# KNOT_v1_0_disp.net
KiCad netlist of a schematic drawn in EAGLE
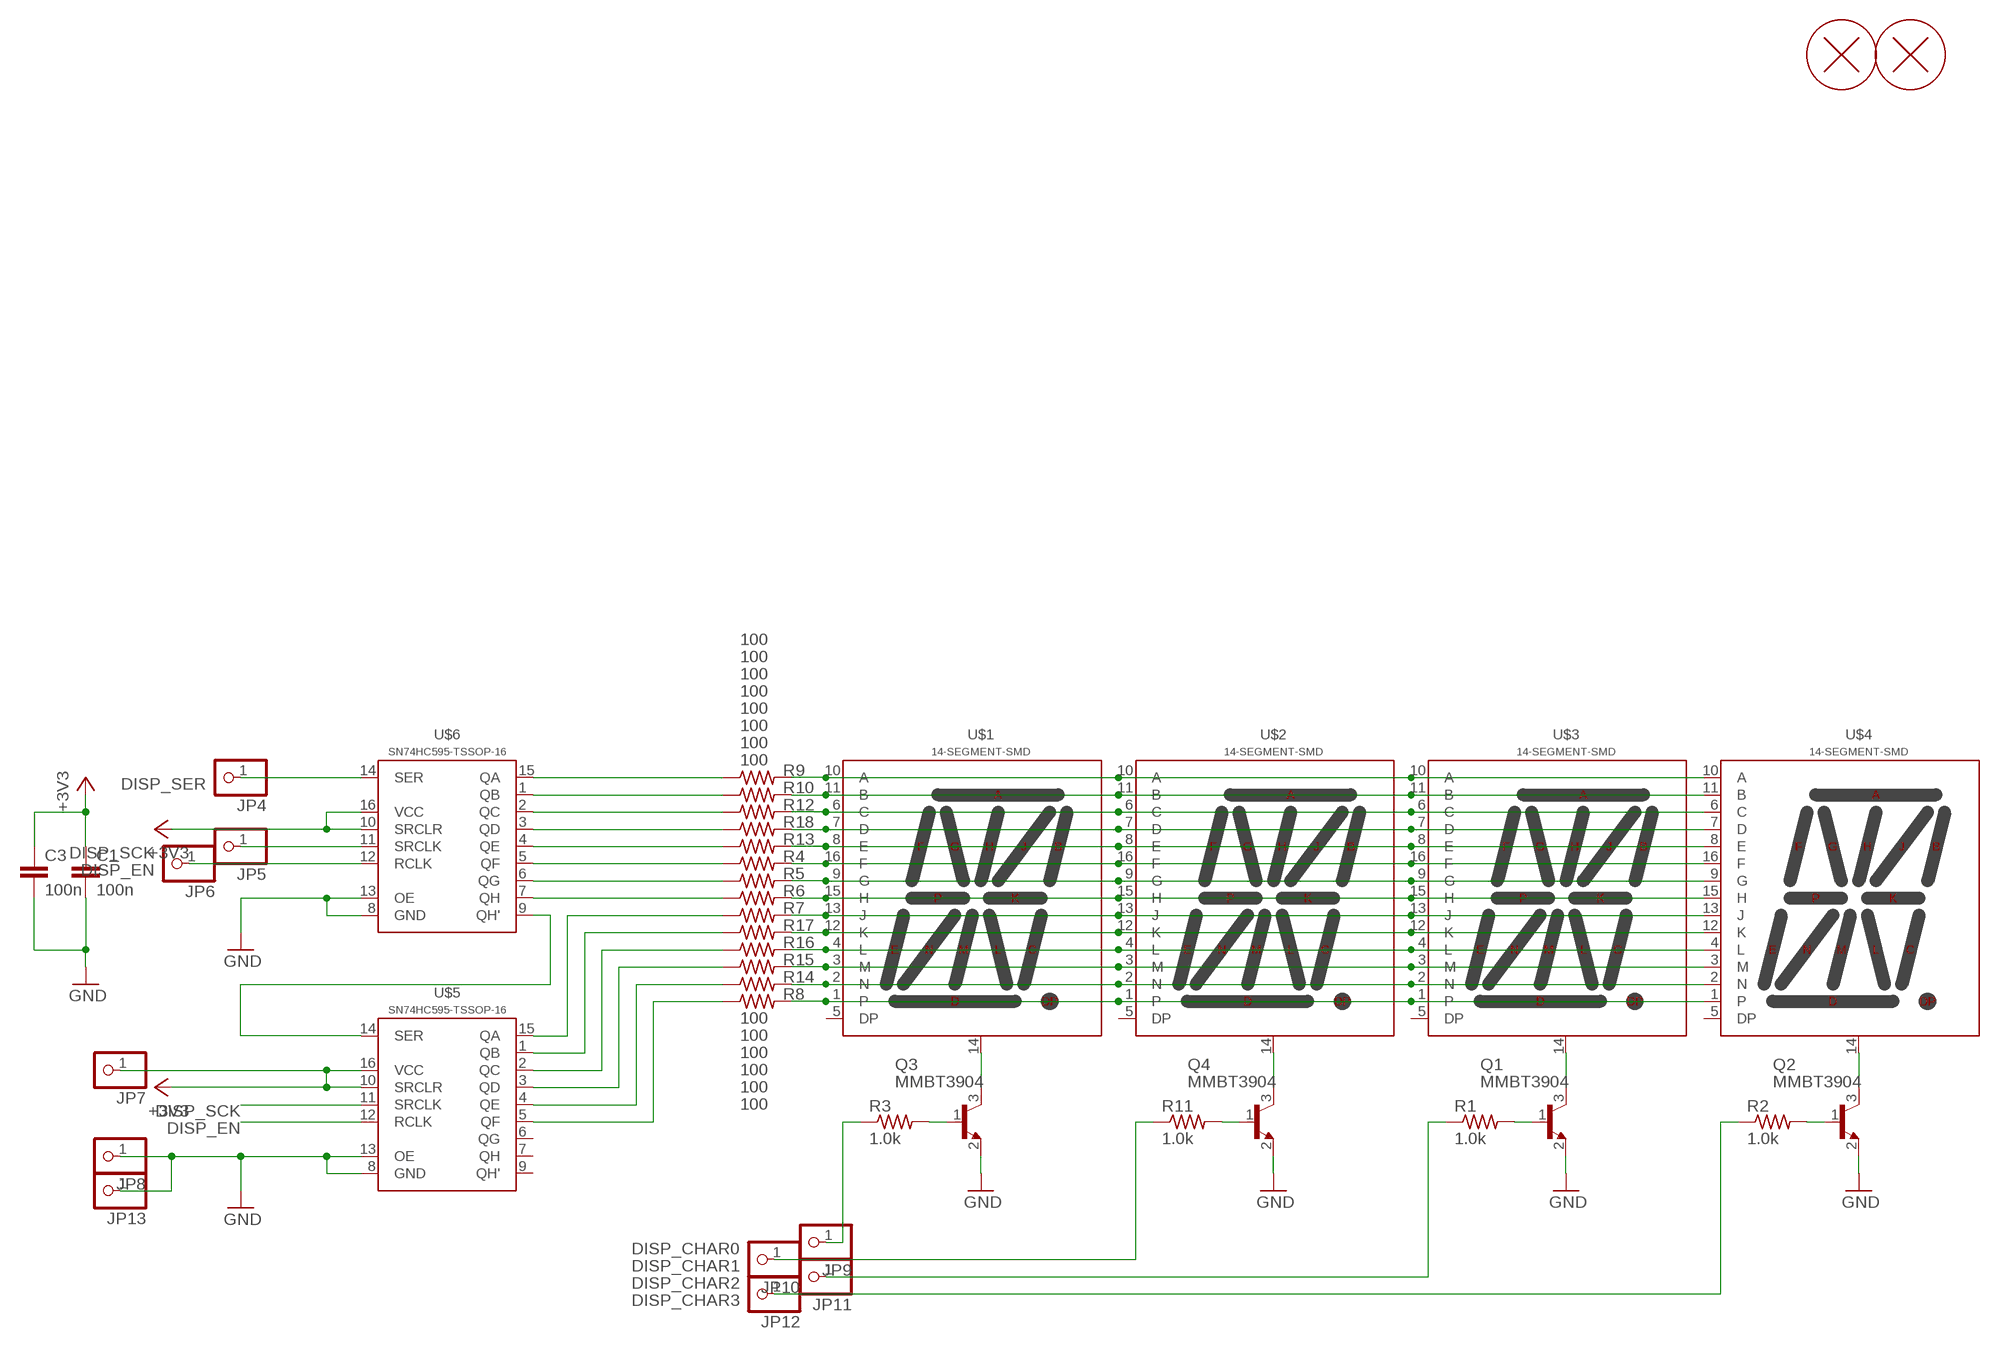
[diagram p0: schematic, sheet 1]

(export (version "E")
  (design (tool "Eeschema 10.0.6"))
  (components
    (comp (ref "C1")
      (value "100n")
      (footprint "eagle-import:RESISTOR_0603")
      (libsource (lib "eagle-import") (part "CAPACITOR"))
    )
    (comp (ref "C3")
      (value "100n")
      (footprint "eagle-import:RESISTOR_0603")
      (libsource (lib "eagle-import") (part "CAPACITOR"))
    )
    (comp (ref "H1")
      (value "PCB_SCREW")
      (footprint "eagle-import:PCB_SCREW")
      (libsource (lib "eagle-import") (part "PCB_SCREW"))
    )
    (comp (ref "H2")
      (value "PCB_SCREW")
      (footprint "eagle-import:PCB_SCREW")
      (libsource (lib "eagle-import") (part "PCB_SCREW"))
    )
    (comp (ref "JP4")
      (value "PINHD-1X1")
      (footprint "eagle-import:1X01")
      (libsource (lib "eagle-import") (part "PINHD-1X1"))
    )
    (comp (ref "JP5")
      (value "PINHD-1X1")
      (footprint "eagle-import:1X01")
      (libsource (lib "eagle-import") (part "PINHD-1X1"))
    )
    (comp (ref "JP6")
      (value "PINHD-1X1")
      (footprint "eagle-import:1X01")
      (libsource (lib "eagle-import") (part "PINHD-1X1"))
    )
    (comp (ref "JP7")
      (value "PINHD-1X1")
      (footprint "eagle-import:1X01")
      (libsource (lib "eagle-import") (part "PINHD-1X1"))
    )
    (comp (ref "JP8")
      (value "PINHD-1X1")
      (footprint "eagle-import:1X01")
      (libsource (lib "eagle-import") (part "PINHD-1X1"))
    )
    (comp (ref "JP9")
      (value "PINHD-1X1")
      (footprint "eagle-import:1X01")
      (libsource (lib "eagle-import") (part "PINHD-1X1"))
    )
    (comp (ref "JP10")
      (value "PINHD-1X1")
      (footprint "eagle-import:1X01")
      (libsource (lib "eagle-import") (part "PINHD-1X1"))
    )
    (comp (ref "JP11")
      (value "PINHD-1X1")
      (footprint "eagle-import:1X01")
      (libsource (lib "eagle-import") (part "PINHD-1X1"))
    )
    (comp (ref "JP12")
      (value "PINHD-1X1")
      (footprint "eagle-import:1X01")
      (libsource (lib "eagle-import") (part "PINHD-1X1"))
    )
    (comp (ref "JP13")
      (value "PINHD-1X1")
      (footprint "eagle-import:1X01")
      (libsource (lib "eagle-import") (part "PINHD-1X1"))
    )
    (comp (ref "Q1")
      (value "MMBT3904")
      (footprint "eagle-import:SOT23")
      (libsource (lib "eagle-import") (part "MMBT3904SOT23"))
    )
    (comp (ref "Q2")
      (value "MMBT3904")
      (footprint "eagle-import:SOT23")
      (libsource (lib "eagle-import") (part "MMBT3904SOT23"))
    )
    (comp (ref "Q3")
      (value "MMBT3904")
      (footprint "eagle-import:SOT23")
      (libsource (lib "eagle-import") (part "MMBT3904SOT23"))
    )
    (comp (ref "Q4")
      (value "MMBT3904")
      (footprint "eagle-import:SOT23")
      (libsource (lib "eagle-import") (part "MMBT3904SOT23"))
    )
    (comp (ref "R1")
      (value "1.0k")
      (footprint "eagle-import:RESISTOR_0603")
      (libsource (lib "eagle-import") (part "RESISTOR"))
    )
    (comp (ref "R2")
      (value "1.0k")
      (footprint "eagle-import:RESISTOR_0603")
      (libsource (lib "eagle-import") (part "RESISTOR"))
    )
    (comp (ref "R3")
      (value "1.0k")
      (footprint "eagle-import:RESISTOR_0603")
      (libsource (lib "eagle-import") (part "RESISTOR"))
    )
    (comp (ref "R4")
      (value "100")
      (footprint "eagle-import:RESISTOR_0603")
      (libsource (lib "eagle-import") (part "RESISTOR"))
    )
    (comp (ref "R5")
      (value "100")
      (footprint "eagle-import:RESISTOR_0603")
      (libsource (lib "eagle-import") (part "RESISTOR"))
    )
    (comp (ref "R6")
      (value "100")
      (footprint "eagle-import:RESISTOR_0603")
      (libsource (lib "eagle-import") (part "RESISTOR"))
    )
    (comp (ref "R7")
      (value "100")
      (footprint "eagle-import:RESISTOR_0603")
      (libsource (lib "eagle-import") (part "RESISTOR"))
    )
    (comp (ref "R8")
      (value "100")
      (footprint "eagle-import:RESISTOR_0603")
      (libsource (lib "eagle-import") (part "RESISTOR"))
    )
    (comp (ref "R9")
      (value "100")
      (footprint "eagle-import:RESISTOR_0603")
      (libsource (lib "eagle-import") (part "RESISTOR"))
    )
    (comp (ref "R10")
      (value "100")
      (footprint "eagle-import:RESISTOR_0603")
      (libsource (lib "eagle-import") (part "RESISTOR"))
    )
    (comp (ref "R11")
      (value "1.0k")
      (footprint "eagle-import:RESISTOR_0603")
      (libsource (lib "eagle-import") (part "RESISTOR"))
    )
    (comp (ref "R12")
      (value "100")
      (footprint "eagle-import:RESISTOR_0603")
      (libsource (lib "eagle-import") (part "RESISTOR"))
    )
    (comp (ref "R13")
      (value "100")
      (footprint "eagle-import:RESISTOR_0603")
      (libsource (lib "eagle-import") (part "RESISTOR"))
    )
    (comp (ref "R14")
      (value "100")
      (footprint "eagle-import:RESISTOR_0603")
      (libsource (lib "eagle-import") (part "RESISTOR"))
    )
    (comp (ref "R15")
      (value "100")
      (footprint "eagle-import:RESISTOR_0603")
      (libsource (lib "eagle-import") (part "RESISTOR"))
    )
    (comp (ref "R16")
      (value "100")
      (footprint "eagle-import:RESISTOR_0603")
      (libsource (lib "eagle-import") (part "RESISTOR"))
    )
    (comp (ref "R17")
      (value "100")
      (footprint "eagle-import:RESISTOR_0603")
      (libsource (lib "eagle-import") (part "RESISTOR"))
    )
    (comp (ref "R18")
      (value "100")
      (footprint "eagle-import:RESISTOR_0603")
      (libsource (lib "eagle-import") (part "RESISTOR"))
    )
    (comp (ref "U$1")
      (value "14-SEGMENT-SMD")
      (footprint "eagle-import:14-SEGMENT-0.4_-SMD")
      (libsource (lib "eagle-import") (part "14-SEGMENT-SMD"))
    )
    (comp (ref "U$2")
      (value "14-SEGMENT-SMD")
      (footprint "eagle-import:14-SEGMENT-0.4_-SMD")
      (libsource (lib "eagle-import") (part "14-SEGMENT-SMD"))
    )
    (comp (ref "U$3")
      (value "14-SEGMENT-SMD")
      (footprint "eagle-import:14-SEGMENT-0.4_-SMD")
      (libsource (lib "eagle-import") (part "14-SEGMENT-SMD"))
    )
    (comp (ref "U$4")
      (value "14-SEGMENT-SMD")
      (footprint "eagle-import:14-SEGMENT-0.4_-SMD")
      (libsource (lib "eagle-import") (part "14-SEGMENT-SMD"))
    )
    (comp (ref "U$5")
      (value "SN74HC595-TSSOP-16")
      (footprint "eagle-import:TSSOP-16")
      (libsource (lib "eagle-import") (part "SN74HC595-TSSOP-16"))
    )
    (comp (ref "U$6")
      (value "SN74HC595-TSSOP-16")
      (footprint "eagle-import:TSSOP-16")
      (libsource (lib "eagle-import") (part "SN74HC595-TSSOP-16"))
    )
  )
  (nets
    (net (code "1") (name "+3V3") (class "Default")
      (node (ref "C1") (pin "1") (pinfunction "1_1") (pintype "passive"))
      (node (ref "C3") (pin "1") (pinfunction "1_1") (pintype "passive"))
      (node (ref "JP7") (pin "1") (pinfunction "1_1") (pintype "passive"))
      (node (ref "U$5") (pin "10") (pinfunction "SRCLR_10") (pintype "bidirectional"))
      (node (ref "U$5") (pin "16") (pinfunction "VCC_16") (pintype "bidirectional"))
      (node (ref "U$6") (pin "10") (pinfunction "SRCLR_10") (pintype "bidirectional"))
      (node (ref "U$6") (pin "16") (pinfunction "VCC_16") (pintype "bidirectional"))
    )
    (net (code "2") (name "/DISP_CHAR0") (class "Default")
      (node (ref "JP9") (pin "1") (pinfunction "1_1") (pintype "passive"))
      (node (ref "R3") (pin "1") (pinfunction "1_1") (pintype "passive"))
    )
    (net (code "3") (name "/DISP_CHAR1") (class "Default")
      (node (ref "JP10") (pin "1") (pinfunction "1_1") (pintype "passive"))
      (node (ref "R11") (pin "1") (pinfunction "1_1") (pintype "passive"))
    )
    (net (code "4") (name "/DISP_CHAR2") (class "Default")
      (node (ref "JP11") (pin "1") (pinfunction "1_1") (pintype "passive"))
      (node (ref "R1") (pin "1") (pinfunction "1_1") (pintype "passive"))
    )
    (net (code "5") (name "/DISP_CHAR3") (class "Default")
      (node (ref "JP12") (pin "1") (pinfunction "1_1") (pintype "passive"))
      (node (ref "R2") (pin "1") (pinfunction "1_1") (pintype "passive"))
    )
    (net (code "6") (name "/DISP_EN") (class "Default")
      (node (ref "JP6") (pin "1") (pinfunction "1_1") (pintype "passive"))
      (node (ref "U$5") (pin "12") (pinfunction "RCLK_12") (pintype "bidirectional"))
      (node (ref "U$6") (pin "12") (pinfunction "RCLK_12") (pintype "bidirectional"))
    )
    (net (code "7") (name "/DISP_SCK") (class "Default")
      (node (ref "JP5") (pin "1") (pinfunction "1_1") (pintype "passive"))
      (node (ref "U$5") (pin "11") (pinfunction "SRCLK_11") (pintype "bidirectional"))
      (node (ref "U$6") (pin "11") (pinfunction "SRCLK_11") (pintype "bidirectional"))
    )
    (net (code "8") (name "/DISP_SER") (class "Default")
      (node (ref "JP4") (pin "1") (pinfunction "1_1") (pintype "passive"))
      (node (ref "U$6") (pin "14") (pinfunction "SER_14") (pintype "bidirectional"))
    )
    (net (code "9") (name "GND") (class "Default")
      (node (ref "C1") (pin "2") (pinfunction "2_2") (pintype "passive"))
      (node (ref "C3") (pin "2") (pinfunction "2_2") (pintype "passive"))
      (node (ref "JP13") (pin "1") (pinfunction "1_1") (pintype "passive"))
      (node (ref "JP8") (pin "1") (pinfunction "1_1") (pintype "passive"))
      (node (ref "Q1") (pin "2") (pinfunction "E_2") (pintype "passive"))
      (node (ref "Q2") (pin "2") (pinfunction "E_2") (pintype "passive"))
      (node (ref "Q3") (pin "2") (pinfunction "E_2") (pintype "passive"))
      (node (ref "Q4") (pin "2") (pinfunction "E_2") (pintype "passive"))
      (node (ref "U$5") (pin "13") (pinfunction "OE_13") (pintype "bidirectional"))
      (node (ref "U$5") (pin "8") (pinfunction "GND_8") (pintype "bidirectional"))
      (node (ref "U$6") (pin "13") (pinfunction "OE_13") (pintype "bidirectional"))
      (node (ref "U$6") (pin "8") (pinfunction "GND_8") (pintype "bidirectional"))
    )
    (net (code "10") (name "Net-(Q1-B)") (class "Default")
      (node (ref "Q1") (pin "1") (pinfunction "B_1") (pintype "passive"))
      (node (ref "R1") (pin "2") (pinfunction "2_2") (pintype "passive"))
    )
    (net (code "11") (name "Net-(Q1-C)") (class "Default")
      (node (ref "Q1") (pin "3") (pinfunction "C_3") (pintype "passive"))
      (node (ref "U$3") (pin "14") (pinfunction "CATHODE_14") (pintype "bidirectional"))
    )
    (net (code "12") (name "Net-(Q2-B)") (class "Default")
      (node (ref "Q2") (pin "1") (pinfunction "B_1") (pintype "passive"))
      (node (ref "R2") (pin "2") (pinfunction "2_2") (pintype "passive"))
    )
    (net (code "13") (name "Net-(Q2-C)") (class "Default")
      (node (ref "Q2") (pin "3") (pinfunction "C_3") (pintype "passive"))
      (node (ref "U$4") (pin "14") (pinfunction "CATHODE_14") (pintype "bidirectional"))
    )
    (net (code "14") (name "Net-(Q3-B)") (class "Default")
      (node (ref "Q3") (pin "1") (pinfunction "B_1") (pintype "passive"))
      (node (ref "R3") (pin "2") (pinfunction "2_2") (pintype "passive"))
    )
    (net (code "15") (name "Net-(Q3-C)") (class "Default")
      (node (ref "Q3") (pin "3") (pinfunction "C_3") (pintype "passive"))
      (node (ref "U$1") (pin "14") (pinfunction "CATHODE_14") (pintype "bidirectional"))
    )
    (net (code "16") (name "Net-(Q4-B)") (class "Default")
      (node (ref "Q4") (pin "1") (pinfunction "B_1") (pintype "passive"))
      (node (ref "R11") (pin "2") (pinfunction "2_2") (pintype "passive"))
    )
    (net (code "17") (name "Net-(Q4-C)") (class "Default")
      (node (ref "Q4") (pin "3") (pinfunction "C_3") (pintype "passive"))
      (node (ref "U$2") (pin "14") (pinfunction "CATHODE_14") (pintype "bidirectional"))
    )
    (net (code "18") (name "Net-(U$1-A)") (class "Default")
      (node (ref "R9") (pin "2") (pinfunction "2_2") (pintype "passive"))
      (node (ref "U$1") (pin "10") (pinfunction "A_10") (pintype "bidirectional"))
      (node (ref "U$2") (pin "10") (pinfunction "A_10") (pintype "bidirectional"))
      (node (ref "U$3") (pin "10") (pinfunction "A_10") (pintype "bidirectional"))
      (node (ref "U$4") (pin "10") (pinfunction "A_10") (pintype "bidirectional"))
    )
    (net (code "19") (name "Net-(U$1-B)") (class "Default")
      (node (ref "R10") (pin "2") (pinfunction "2_2") (pintype "passive"))
      (node (ref "U$1") (pin "11") (pinfunction "B_11") (pintype "bidirectional"))
      (node (ref "U$2") (pin "11") (pinfunction "B_11") (pintype "bidirectional"))
      (node (ref "U$3") (pin "11") (pinfunction "B_11") (pintype "bidirectional"))
      (node (ref "U$4") (pin "11") (pinfunction "B_11") (pintype "bidirectional"))
    )
    (net (code "20") (name "Net-(U$1-C)") (class "Default")
      (node (ref "R12") (pin "2") (pinfunction "2_2") (pintype "passive"))
      (node (ref "U$1") (pin "6") (pinfunction "C_6") (pintype "bidirectional"))
      (node (ref "U$2") (pin "6") (pinfunction "C_6") (pintype "bidirectional"))
      (node (ref "U$3") (pin "6") (pinfunction "C_6") (pintype "bidirectional"))
      (node (ref "U$4") (pin "6") (pinfunction "C_6") (pintype "bidirectional"))
    )
    (net (code "21") (name "Net-(U$1-D)") (class "Default")
      (node (ref "R18") (pin "2") (pinfunction "2_2") (pintype "passive"))
      (node (ref "U$1") (pin "7") (pinfunction "D_7") (pintype "bidirectional"))
      (node (ref "U$2") (pin "7") (pinfunction "D_7") (pintype "bidirectional"))
      (node (ref "U$3") (pin "7") (pinfunction "D_7") (pintype "bidirectional"))
      (node (ref "U$4") (pin "7") (pinfunction "D_7") (pintype "bidirectional"))
    )
    (net (code "22") (name "Net-(U$1-E)") (class "Default")
      (node (ref "R13") (pin "2") (pinfunction "2_2") (pintype "passive"))
      (node (ref "U$1") (pin "8") (pinfunction "E_8") (pintype "bidirectional"))
      (node (ref "U$2") (pin "8") (pinfunction "E_8") (pintype "bidirectional"))
      (node (ref "U$3") (pin "8") (pinfunction "E_8") (pintype "bidirectional"))
      (node (ref "U$4") (pin "8") (pinfunction "E_8") (pintype "bidirectional"))
    )
    (net (code "23") (name "Net-(U$1-F)") (class "Default")
      (node (ref "R4") (pin "2") (pinfunction "2_2") (pintype "passive"))
      (node (ref "U$1") (pin "16") (pinfunction "F_16") (pintype "bidirectional"))
      (node (ref "U$2") (pin "16") (pinfunction "F_16") (pintype "bidirectional"))
      (node (ref "U$3") (pin "16") (pinfunction "F_16") (pintype "bidirectional"))
      (node (ref "U$4") (pin "16") (pinfunction "F_16") (pintype "bidirectional"))
    )
    (net (code "24") (name "Net-(U$1-G)") (class "Default")
      (node (ref "R5") (pin "2") (pinfunction "2_2") (pintype "passive"))
      (node (ref "U$1") (pin "9") (pinfunction "G_9") (pintype "bidirectional"))
      (node (ref "U$2") (pin "9") (pinfunction "G_9") (pintype "bidirectional"))
      (node (ref "U$3") (pin "9") (pinfunction "G_9") (pintype "bidirectional"))
      (node (ref "U$4") (pin "9") (pinfunction "G_9") (pintype "bidirectional"))
    )
    (net (code "25") (name "Net-(U$1-H)") (class "Default")
      (node (ref "R6") (pin "2") (pinfunction "2_2") (pintype "passive"))
      (node (ref "U$1") (pin "15") (pinfunction "H_15") (pintype "bidirectional"))
      (node (ref "U$2") (pin "15") (pinfunction "H_15") (pintype "bidirectional"))
      (node (ref "U$3") (pin "15") (pinfunction "H_15") (pintype "bidirectional"))
      (node (ref "U$4") (pin "15") (pinfunction "H_15") (pintype "bidirectional"))
    )
    (net (code "26") (name "Net-(U$1-J)") (class "Default")
      (node (ref "R7") (pin "2") (pinfunction "2_2") (pintype "passive"))
      (node (ref "U$1") (pin "13") (pinfunction "J_13") (pintype "bidirectional"))
      (node (ref "U$2") (pin "13") (pinfunction "J_13") (pintype "bidirectional"))
      (node (ref "U$3") (pin "13") (pinfunction "J_13") (pintype "bidirectional"))
      (node (ref "U$4") (pin "13") (pinfunction "J_13") (pintype "bidirectional"))
    )
    (net (code "27") (name "Net-(U$1-K)") (class "Default")
      (node (ref "R17") (pin "2") (pinfunction "2_2") (pintype "passive"))
      (node (ref "U$1") (pin "12") (pinfunction "K_12") (pintype "bidirectional"))
      (node (ref "U$2") (pin "12") (pinfunction "K_12") (pintype "bidirectional"))
      (node (ref "U$3") (pin "12") (pinfunction "K_12") (pintype "bidirectional"))
      (node (ref "U$4") (pin "12") (pinfunction "K_12") (pintype "bidirectional"))
    )
    (net (code "28") (name "Net-(U$1-L)") (class "Default")
      (node (ref "R16") (pin "2") (pinfunction "2_2") (pintype "passive"))
      (node (ref "U$1") (pin "4") (pinfunction "L_4") (pintype "bidirectional"))
      (node (ref "U$2") (pin "4") (pinfunction "L_4") (pintype "bidirectional"))
      (node (ref "U$3") (pin "4") (pinfunction "L_4") (pintype "bidirectional"))
      (node (ref "U$4") (pin "4") (pinfunction "L_4") (pintype "bidirectional"))
    )
    (net (code "29") (name "Net-(U$1-M)") (class "Default")
      (node (ref "R15") (pin "2") (pinfunction "2_2") (pintype "passive"))
      (node (ref "U$1") (pin "3") (pinfunction "M_3") (pintype "bidirectional"))
      (node (ref "U$2") (pin "3") (pinfunction "M_3") (pintype "bidirectional"))
      (node (ref "U$3") (pin "3") (pinfunction "M_3") (pintype "bidirectional"))
      (node (ref "U$4") (pin "3") (pinfunction "M_3") (pintype "bidirectional"))
    )
    (net (code "30") (name "Net-(U$1-N)") (class "Default")
      (node (ref "R14") (pin "2") (pinfunction "2_2") (pintype "passive"))
      (node (ref "U$1") (pin "2") (pinfunction "N_2") (pintype "bidirectional"))
      (node (ref "U$2") (pin "2") (pinfunction "N_2") (pintype "bidirectional"))
      (node (ref "U$3") (pin "2") (pinfunction "N_2") (pintype "bidirectional"))
      (node (ref "U$4") (pin "2") (pinfunction "N_2") (pintype "bidirectional"))
    )
    (net (code "31") (name "Net-(U$1-P)") (class "Default")
      (node (ref "R8") (pin "2") (pinfunction "2_2") (pintype "passive"))
      (node (ref "U$1") (pin "1") (pinfunction "P_1") (pintype "bidirectional"))
      (node (ref "U$2") (pin "1") (pinfunction "P_1") (pintype "bidirectional"))
      (node (ref "U$3") (pin "1") (pinfunction "P_1") (pintype "bidirectional"))
      (node (ref "U$4") (pin "1") (pinfunction "P_1") (pintype "bidirectional"))
    )
    (net (code "32") (name "Net-(U$5-QA)") (class "Default")
      (node (ref "R7") (pin "1") (pinfunction "1_1") (pintype "passive"))
      (node (ref "U$5") (pin "15") (pinfunction "QA_15") (pintype "bidirectional"))
    )
    (net (code "33") (name "Net-(U$5-QB)") (class "Default")
      (node (ref "R17") (pin "1") (pinfunction "1_1") (pintype "passive"))
      (node (ref "U$5") (pin "1") (pinfunction "QB_1") (pintype "bidirectional"))
    )
    (net (code "34") (name "Net-(U$5-QC)") (class "Default")
      (node (ref "R16") (pin "1") (pinfunction "1_1") (pintype "passive"))
      (node (ref "U$5") (pin "2") (pinfunction "QC_2") (pintype "bidirectional"))
    )
    (net (code "35") (name "Net-(U$5-QD)") (class "Default")
      (node (ref "R15") (pin "1") (pinfunction "1_1") (pintype "passive"))
      (node (ref "U$5") (pin "3") (pinfunction "QD_3") (pintype "bidirectional"))
    )
    (net (code "36") (name "Net-(U$5-QE)") (class "Default")
      (node (ref "R14") (pin "1") (pinfunction "1_1") (pintype "passive"))
      (node (ref "U$5") (pin "4") (pinfunction "QE_4") (pintype "bidirectional"))
    )
    (net (code "37") (name "Net-(U$5-QF)") (class "Default")
      (node (ref "R8") (pin "1") (pinfunction "1_1") (pintype "passive"))
      (node (ref "U$5") (pin "5") (pinfunction "QF_5") (pintype "bidirectional"))
    )
    (net (code "38") (name "Net-(U$5-SER)") (class "Default")
      (node (ref "U$5") (pin "14") (pinfunction "SER_14") (pintype "bidirectional"))
      (node (ref "U$6") (pin "9") (pinfunction "QH'_9") (pintype "bidirectional"))
    )
    (net (code "39") (name "Net-(U$6-QA)") (class "Default")
      (node (ref "R9") (pin "1") (pinfunction "1_1") (pintype "passive"))
      (node (ref "U$6") (pin "15") (pinfunction "QA_15") (pintype "bidirectional"))
    )
    (net (code "40") (name "Net-(U$6-QB)") (class "Default")
      (node (ref "R10") (pin "1") (pinfunction "1_1") (pintype "passive"))
      (node (ref "U$6") (pin "1") (pinfunction "QB_1") (pintype "bidirectional"))
    )
    (net (code "41") (name "Net-(U$6-QC)") (class "Default")
      (node (ref "R12") (pin "1") (pinfunction "1_1") (pintype "passive"))
      (node (ref "U$6") (pin "2") (pinfunction "QC_2") (pintype "bidirectional"))
    )
    (net (code "42") (name "Net-(U$6-QD)") (class "Default")
      (node (ref "R18") (pin "1") (pinfunction "1_1") (pintype "passive"))
      (node (ref "U$6") (pin "3") (pinfunction "QD_3") (pintype "bidirectional"))
    )
    (net (code "43") (name "Net-(U$6-QE)") (class "Default")
      (node (ref "R13") (pin "1") (pinfunction "1_1") (pintype "passive"))
      (node (ref "U$6") (pin "4") (pinfunction "QE_4") (pintype "bidirectional"))
    )
    (net (code "44") (name "Net-(U$6-QF)") (class "Default")
      (node (ref "R4") (pin "1") (pinfunction "1_1") (pintype "passive"))
      (node (ref "U$6") (pin "5") (pinfunction "QF_5") (pintype "bidirectional"))
    )
    (net (code "45") (name "Net-(U$6-QG)") (class "Default")
      (node (ref "R5") (pin "1") (pinfunction "1_1") (pintype "passive"))
      (node (ref "U$6") (pin "6") (pinfunction "QG_6") (pintype "bidirectional"))
    )
    (net (code "46") (name "Net-(U$6-QH)") (class "Default")
      (node (ref "R6") (pin "1") (pinfunction "1_1") (pintype "passive"))
      (node (ref "U$6") (pin "7") (pinfunction "QH_7") (pintype "bidirectional"))
    )
    (net (code "47") (name "unconnected-(U$1-DP-Pad5)") (class "Default")
      (node (ref "U$1") (pin "5") (pinfunction "DP_5") (pintype "bidirectional"))
    )
    (net (code "48") (name "unconnected-(U$2-DP-Pad5)") (class "Default")
      (node (ref "U$2") (pin "5") (pinfunction "DP_5") (pintype "bidirectional"))
    )
    (net (code "49") (name "unconnected-(U$3-DP-Pad5)") (class "Default")
      (node (ref "U$3") (pin "5") (pinfunction "DP_5") (pintype "bidirectional"))
    )
    (net (code "50") (name "unconnected-(U$4-DP-Pad5)") (class "Default")
      (node (ref "U$4") (pin "5") (pinfunction "DP_5") (pintype "bidirectional"))
    )
    (net (code "51") (name "unconnected-(U$5-QG-Pad6)") (class "Default")
      (node (ref "U$5") (pin "6") (pinfunction "QG_6") (pintype "bidirectional"))
    )
    (net (code "52") (name "unconnected-(U$5-QH'-Pad9)") (class "Default")
      (node (ref "U$5") (pin "9") (pinfunction "QH'_9") (pintype "bidirectional"))
    )
    (net (code "53") (name "unconnected-(U$5-QH-Pad7)") (class "Default")
      (node (ref "U$5") (pin "7") (pinfunction "QH_7") (pintype "bidirectional"))
    )
  )
)
